# Aegaeon_REV_B_20130222.net
KiCad netlist of a schematic drawn in EAGLE
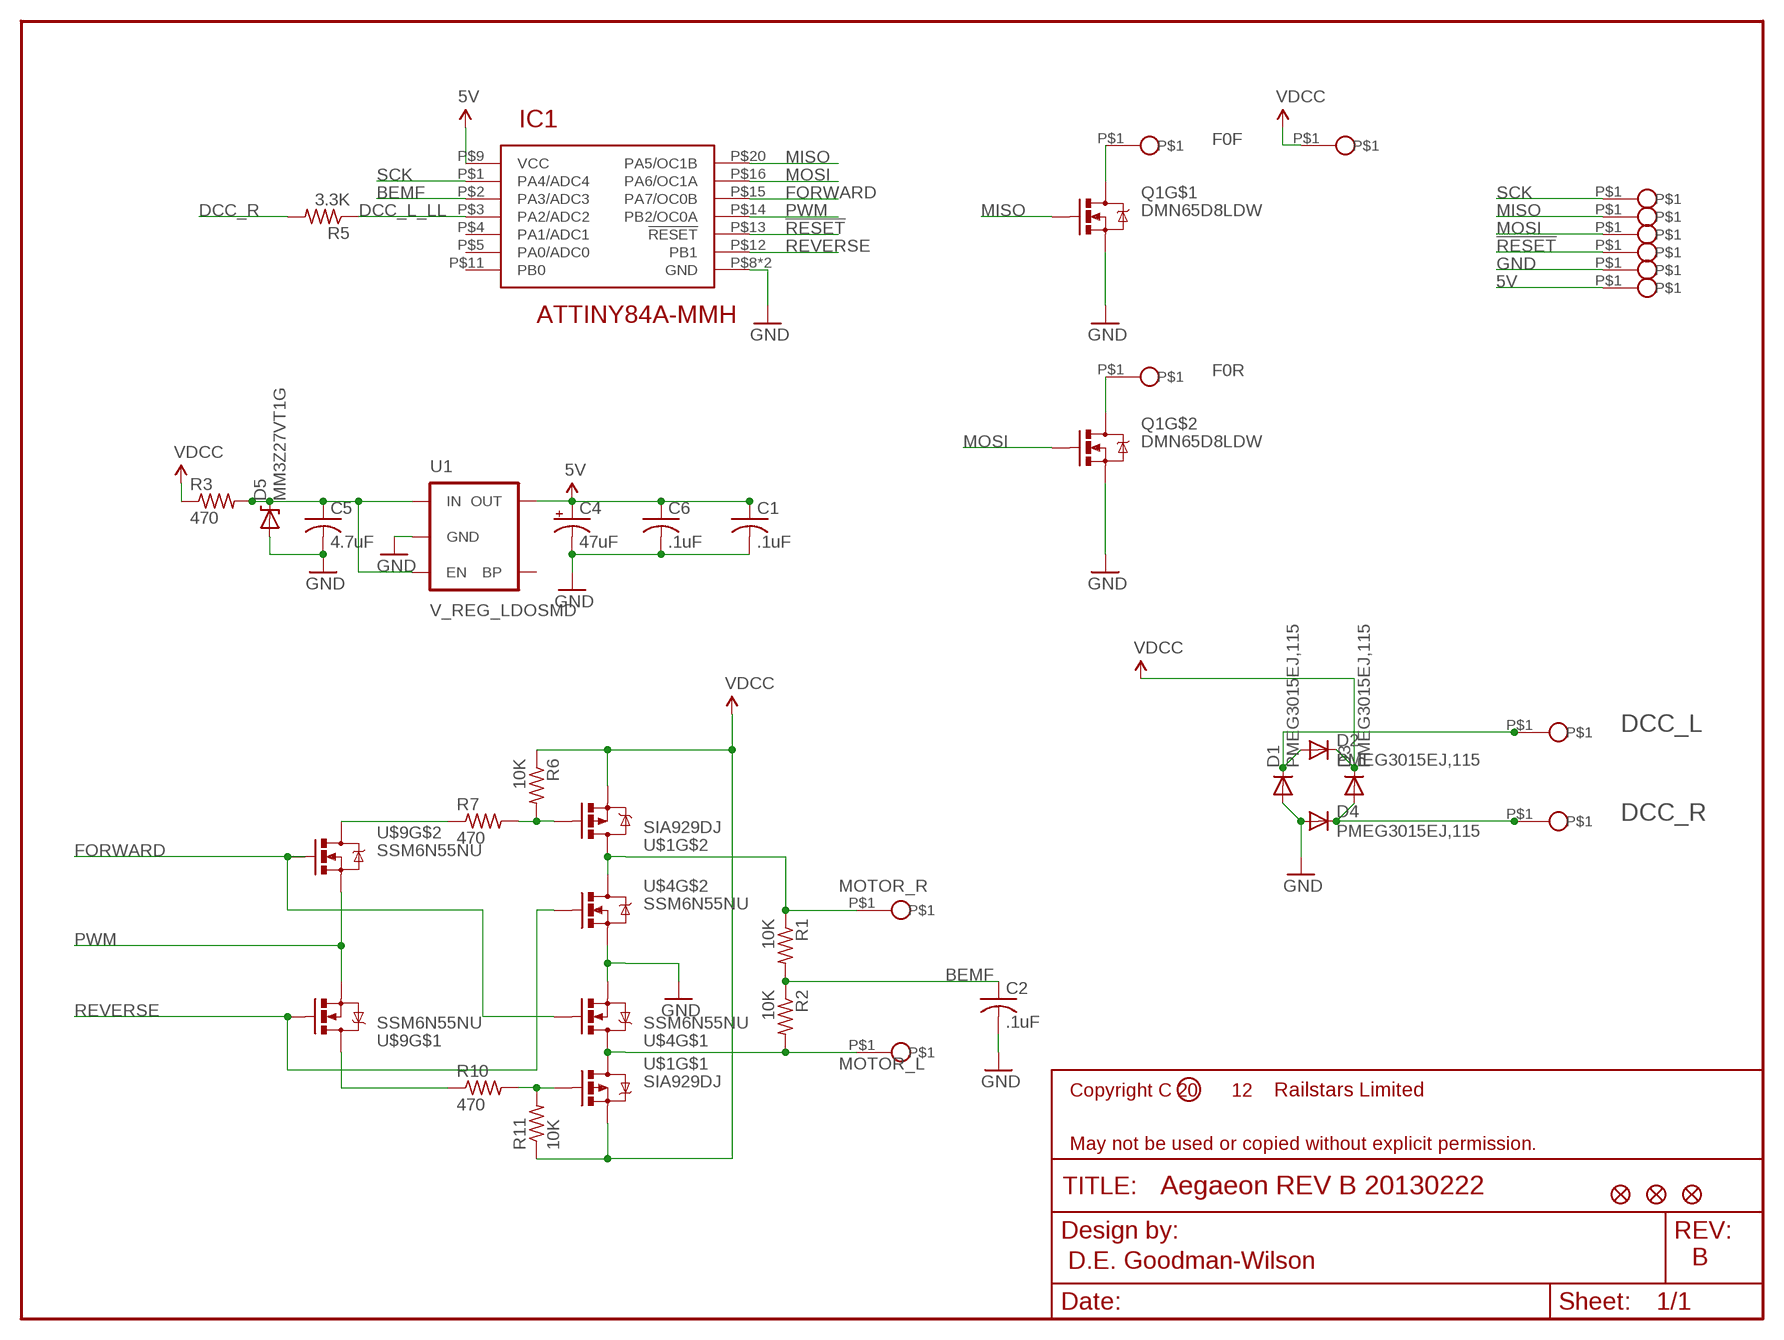
[diagram p0: schematic, sheet 1]

(export (version "E")
  (design (tool "Eeschema 10.0.6"))
  (components
    (comp (ref "C1")
      (value ".1uF")
      (footprint "eagle-import:C0201")
      (libsource (lib "eagle-import") (part "C-USC0201"))
    )
    (comp (ref "C2")
      (value ".1uF")
      (footprint "eagle-import:C0402")
      (libsource (lib "eagle-import") (part "C-USC0402"))
    )
    (comp (ref "C4")
      (value "47uF")
      (footprint "eagle-import:CPOL0603")
      (libsource (lib "eagle-import") (part "CPOL-USF980J476MMA"))
    )
    (comp (ref "C5")
      (value "4.7uF")
      (footprint "eagle-import:C0603")
      (libsource (lib "eagle-import") (part "C-USC0603"))
    )
    (comp (ref "C6")
      (value ".1uF")
      (footprint "eagle-import:C0402")
      (libsource (lib "eagle-import") (part "C-USC0402"))
    )
    (comp (ref "D1")
      (value "PMEG3015EJ,115")
      (footprint "eagle-import:SOD-323")
      (libsource (lib "eagle-import") (part "DIODESOD"))
    )
    (comp (ref "D2")
      (value "PMEG3015EJ,115")
      (footprint "eagle-import:SOD-323")
      (libsource (lib "eagle-import") (part "DIODESOD"))
    )
    (comp (ref "D3")
      (value "PMEG3015EJ,115")
      (footprint "eagle-import:SOD-323")
      (libsource (lib "eagle-import") (part "DIODESOD"))
    )
    (comp (ref "D4")
      (value "PMEG3015EJ,115")
      (footprint "eagle-import:SOD-323")
      (libsource (lib "eagle-import") (part "DIODESOD"))
    )
    (comp (ref "D5")
      (value "MM3Z27VT1G")
      (footprint "eagle-import:SOD-323")
      (libsource (lib "eagle-import") (part "DIODE-ZENER-BZT52"))
    )
    (comp (ref "DCC_L")
      (value "PAD1MM")
      (footprint "eagle-import:LED_SOLDER_PAD")
      (libsource (lib "eagle-import") (part "PAD1MM"))
    )
    (comp (ref "DCC_R")
      (value "PAD1MM")
      (footprint "eagle-import:LED_SOLDER_PAD")
      (libsource (lib "eagle-import") (part "PAD1MM"))
    )
    (comp (ref "IC1")
      (value "ATTINY84A-MMH")
      (footprint "eagle-import:VQFN-20")
      (libsource (lib "eagle-import") (part "ATTINY84A-MMH"))
    )
    (comp (ref "JP1")
      (value "FIDUCIALUFIDUCIAL")
      (footprint "eagle-import:MICRO-FIDUCIAL")
      (libsource (lib "eagle-import") (part "FIDUCIALUFIDUCIAL"))
    )
    (comp (ref "JP2")
      (value "FIDUCIALUFIDUCIAL")
      (footprint "eagle-import:MICRO-FIDUCIAL")
      (libsource (lib "eagle-import") (part "FIDUCIALUFIDUCIAL"))
    )
    (comp (ref "JP4")
      (value "FIDUCIALUFIDUCIAL")
      (footprint "eagle-import:MICRO-FIDUCIAL")
      (libsource (lib "eagle-import") (part "FIDUCIALUFIDUCIAL"))
    )
    (comp (ref "Q1")
      (value "DMN65D8LDW")
      (footprint "eagle-import:SOT363")
      (libsource (lib "eagle-import") (part "DMN65D8LDW"))
    )
    (comp (ref "R1")
      (value "10K")
      (footprint "eagle-import:R0201")
      (libsource (lib "eagle-import") (part "R-US_R0201"))
    )
    (comp (ref "R2")
      (value "10K")
      (footprint "eagle-import:R0201")
      (libsource (lib "eagle-import") (part "R-US_R0201"))
    )
    (comp (ref "R3")
      (value "470")
      (footprint "eagle-import:R0201")
      (libsource (lib "eagle-import") (part "R-US_R0201"))
    )
    (comp (ref "R5")
      (value "3.3K")
      (footprint "eagle-import:R0201")
      (libsource (lib "eagle-import") (part "R-US_R0201"))
    )
    (comp (ref "R6")
      (value "10K")
      (footprint "eagle-import:R0201")
      (libsource (lib "eagle-import") (part "R-US_R0201"))
    )
    (comp (ref "R7")
      (value "470")
      (footprint "eagle-import:R0201")
      (libsource (lib "eagle-import") (part "R-US_R0201"))
    )
    (comp (ref "R10")
      (value "470")
      (footprint "eagle-import:R0201")
      (libsource (lib "eagle-import") (part "R-US_R0201"))
    )
    (comp (ref "R11")
      (value "10K")
      (footprint "eagle-import:R0201")
      (libsource (lib "eagle-import") (part "R-US_R0201"))
    )
    (comp (ref "U$1")
      (value "SIA929DJ")
      (footprint "eagle-import:SC70-6L")
      (libsource (lib "eagle-import") (part "SIA929DJ"))
    )
    (comp (ref "U$2")
      (value "PAD1MM")
      (footprint "eagle-import:LED_SOLDER_PAD")
      (libsource (lib "eagle-import") (part "PAD1MM"))
    )
    (comp (ref "U$3")
      (value "PAD1MM")
      (footprint "eagle-import:LED_SOLDER_PAD")
      (libsource (lib "eagle-import") (part "PAD1MM"))
    )
    (comp (ref "U$4")
      (value "SSM6N55NU")
      (footprint "eagle-import:UDFN6")
      (libsource (lib "eagle-import") (part "SSM6N55NU"))
    )
    (comp (ref "U$5")
      (value "PAD1MM")
      (footprint "eagle-import:LED_SOLDER_PAD")
      (libsource (lib "eagle-import") (part "PAD1MM"))
    )
    (comp (ref "U$9")
      (value "SSM6N55NU")
      (footprint "eagle-import:UDFN6")
      (libsource (lib "eagle-import") (part "SSM6N55NU"))
    )
    (comp (ref "U$10")
      (value "PAD1MM")
      (footprint "eagle-import:LED_SOLDER_PAD")
      (libsource (lib "eagle-import") (part "PAD1MM"))
    )
    (comp (ref "U$11")
      (value "PAD1MM")
      (footprint "eagle-import:LED_SOLDER_PAD")
      (libsource (lib "eagle-import") (part "PAD1MM"))
    )
    (comp (ref "U$14")
      (value "PAD.75MM")
      (footprint "eagle-import:POGO_PAD")
      (libsource (lib "eagle-import") (part "PAD.75MM"))
    )
    (comp (ref "U$15")
      (value "PAD.75MM")
      (footprint "eagle-import:POGO_PAD")
      (libsource (lib "eagle-import") (part "PAD.75MM"))
    )
    (comp (ref "U$16")
      (value "PAD.75MM")
      (footprint "eagle-import:POGO_PAD")
      (libsource (lib "eagle-import") (part "PAD.75MM"))
    )
    (comp (ref "U$17")
      (value "PAD.75MM")
      (footprint "eagle-import:POGO_PAD")
      (libsource (lib "eagle-import") (part "PAD.75MM"))
    )
    (comp (ref "U$18")
      (value "PAD.75MM")
      (footprint "eagle-import:POGO_PAD")
      (libsource (lib "eagle-import") (part "PAD.75MM"))
    )
    (comp (ref "U$19")
      (value "PAD.75MM")
      (footprint "eagle-import:POGO_PAD")
      (libsource (lib "eagle-import") (part "PAD.75MM"))
    )
    (comp (ref "U1")
      (value "V_REG_LDOSMD")
      (footprint "eagle-import:SOT23-5")
      (libsource (lib "eagle-import") (part "V_REG_LDOSMD"))
    )
  )
  (nets
    (net (code "1") (name "/BEMF") (class "Default")
      (node (ref "C2") (pin "1") (pinfunction "1_1") (pintype "passive"))
      (node (ref "IC1") (pin "P$2") (pinfunction "PA3/ADC3_P$2") (pintype "bidirectional"))
      (node (ref "R1") (pin "2") (pinfunction "2_2") (pintype "passive"))
      (node (ref "R2") (pin "1") (pinfunction "1_1") (pintype "passive"))
    )
    (net (code "2") (name "/DCC_L") (class "Default")
      (node (ref "D1") (pin "1") (pinfunction "C_1") (pintype "passive"))
      (node (ref "D2") (pin "2") (pinfunction "A_2") (pintype "passive"))
      (node (ref "DCC_L") (pin "P$1") (pinfunction "P$1_P$1") (pintype "bidirectional"))
    )
    (net (code "3") (name "/DCC_L_LL") (class "Default")
      (node (ref "IC1") (pin "P$3") (pinfunction "PA2/ADC2_P$3") (pintype "bidirectional"))
      (node (ref "R5") (pin "1") (pinfunction "1_1") (pintype "passive"))
    )
    (net (code "4") (name "/DCC_R") (class "Default")
      (node (ref "D3") (pin "2") (pinfunction "A_2") (pintype "passive"))
      (node (ref "D4") (pin "1") (pinfunction "C_1") (pintype "passive"))
      (node (ref "DCC_R") (pin "P$1") (pinfunction "P$1_P$1") (pintype "bidirectional"))
      (node (ref "R5") (pin "2") (pinfunction "2_2") (pintype "passive"))
    )
    (net (code "5") (name "/F0F") (class "Default")
      (node (ref "Q1") (pin "P$4") (pinfunction "D_P$4") (pintype "passive"))
      (node (ref "U$10") (pin "P$1") (pinfunction "P$1_P$1") (pintype "bidirectional"))
    )
    (net (code "6") (name "/F0R") (class "Default")
      (node (ref "Q1") (pin "P$1") (pinfunction "D_P$1") (pintype "passive"))
      (node (ref "U$5") (pin "P$1") (pinfunction "P$1_P$1") (pintype "bidirectional"))
    )
    (net (code "7") (name "/FORWARD") (class "Default")
      (node (ref "IC1") (pin "P$15") (pinfunction "PA7/OC0B_P$15") (pintype "bidirectional"))
      (node (ref "U$4") (pin "G1") (pinfunction "G_G1") (pintype "passive"))
      (node (ref "U$9") (pin "G2") (pinfunction "G_G2") (pintype "passive"))
    )
    (net (code "8") (name "/MISO") (class "Default")
      (node (ref "IC1") (pin "P$20") (pinfunction "PA5/OC1B_P$20") (pintype "bidirectional"))
      (node (ref "Q1") (pin "P$2") (pinfunction "G_P$2") (pintype "passive"))
      (node (ref "U$15") (pin "P$1") (pinfunction "P$1_P$1") (pintype "bidirectional"))
    )
    (net (code "9") (name "/MOSI") (class "Default")
      (node (ref "IC1") (pin "P$16") (pinfunction "PA6/OC1A_P$16") (pintype "bidirectional"))
      (node (ref "Q1") (pin "P$5") (pinfunction "G_P$5") (pintype "passive"))
      (node (ref "U$16") (pin "P$1") (pinfunction "P$1_P$1") (pintype "bidirectional"))
    )
    (net (code "10") (name "/MOTOR_L") (class "Default")
      (node (ref "R2") (pin "2") (pinfunction "2_2") (pintype "passive"))
      (node (ref "U$1") (pin "D1") (pinfunction "D_D1") (pintype "passive"))
      (node (ref "U$1") (pin "D1$2") (pinfunction "D_D1$2") (pintype "passive"))
      (node (ref "U$3") (pin "P$1") (pinfunction "P$1_P$1") (pintype "bidirectional"))
      (node (ref "U$4") (pin "D1") (pinfunction "D_D1") (pintype "passive"))
      (node (ref "U$4") (pin "D1$1") (pinfunction "D_D1$1") (pintype "passive"))
    )
    (net (code "11") (name "/MOTOR_R") (class "Default")
      (node (ref "R1") (pin "1") (pinfunction "1_1") (pintype "passive"))
      (node (ref "U$1") (pin "D2") (pinfunction "D_D2") (pintype "passive"))
      (node (ref "U$1") (pin "D2$2") (pinfunction "D_D2$2") (pintype "passive"))
      (node (ref "U$2") (pin "P$1") (pinfunction "P$1_P$1") (pintype "bidirectional"))
      (node (ref "U$4") (pin "D2") (pinfunction "D_D2") (pintype "passive"))
      (node (ref "U$4") (pin "D2$2") (pinfunction "D_D2$2") (pintype "passive"))
    )
    (net (code "12") (name "/PWM") (class "Default")
      (node (ref "IC1") (pin "P$14") (pinfunction "PB2/OC0A_P$14") (pintype "bidirectional"))
      (node (ref "U$9") (pin "S1") (pinfunction "S_S1") (pintype "passive"))
      (node (ref "U$9") (pin "S2") (pinfunction "S_S2") (pintype "passive"))
    )
    (net (code "13") (name "/REVERSE") (class "Default")
      (node (ref "IC1") (pin "P$12") (pinfunction "PB1_P$12") (pintype "bidirectional"))
      (node (ref "U$4") (pin "G2") (pinfunction "G_G2") (pintype "passive"))
      (node (ref "U$9") (pin "G1") (pinfunction "G_G1") (pintype "passive"))
    )
    (net (code "14") (name "/SCK") (class "Default")
      (node (ref "IC1") (pin "P$1") (pinfunction "PA4/ADC4_P$1") (pintype "bidirectional"))
      (node (ref "U$14") (pin "P$1") (pinfunction "P$1_P$1") (pintype "bidirectional"))
    )
    (net (code "15") (name "/~{RESET}") (class "Default")
      (node (ref "IC1") (pin "P$13") (pinfunction "~{RESET}_P$13") (pintype "bidirectional"))
      (node (ref "U$17") (pin "P$1") (pinfunction "P$1_P$1") (pintype "bidirectional"))
    )
    (net (code "16") (name "5V") (class "Default")
      (node (ref "C1") (pin "1") (pinfunction "1_1") (pintype "passive"))
      (node (ref "C4") (pin "1") (pinfunction "+_1") (pintype "passive"))
      (node (ref "C6") (pin "1") (pinfunction "1_1") (pintype "passive"))
      (node (ref "IC1") (pin "P$9") (pinfunction "VCC_P$9") (pintype "bidirectional"))
      (node (ref "U$19") (pin "P$1") (pinfunction "P$1_P$1") (pintype "bidirectional"))
      (node (ref "U1") (pin "5") (pinfunction "OUT_5") (pintype "passive"))
    )
    (net (code "17") (name "GND") (class "Default")
      (node (ref "C1") (pin "2") (pinfunction "2_2") (pintype "passive"))
      (node (ref "C2") (pin "2") (pinfunction "2_2") (pintype "passive"))
      (node (ref "C4") (pin "2") (pinfunction "-_2") (pintype "passive"))
      (node (ref "C5") (pin "2") (pinfunction "2_2") (pintype "passive"))
      (node (ref "C6") (pin "2") (pinfunction "2_2") (pintype "passive"))
      (node (ref "D1") (pin "2") (pinfunction "A_2") (pintype "passive"))
      (node (ref "D4") (pin "2") (pinfunction "A_2") (pintype "passive"))
      (node (ref "D5") (pin "2") (pinfunction "A_2") (pintype "passive"))
      (node (ref "IC1") (pin "P$21") (pinfunction "GND_P$21") (pintype "bidirectional"))
      (node (ref "IC1") (pin "P$8") (pinfunction "GND_P$8") (pintype "bidirectional"))
      (node (ref "Q1") (pin "P$3") (pinfunction "S_P$3") (pintype "passive"))
      (node (ref "Q1") (pin "P$6") (pinfunction "S_P$6") (pintype "passive"))
      (node (ref "U$18") (pin "P$1") (pinfunction "P$1_P$1") (pintype "bidirectional"))
      (node (ref "U$4") (pin "S1") (pinfunction "S_S1") (pintype "passive"))
      (node (ref "U$4") (pin "S2") (pinfunction "S_S2") (pintype "passive"))
      (node (ref "U1") (pin "2") (pinfunction "GND_2") (pintype "input"))
    )
    (net (code "18") (name "Net-(D5-C)") (class "Default")
      (node (ref "C5") (pin "1") (pinfunction "1_1") (pintype "passive"))
      (node (ref "D5") (pin "1") (pinfunction "C_1") (pintype "passive"))
      (node (ref "R3") (pin "2") (pinfunction "2_2") (pintype "passive"))
      (node (ref "U1") (pin "1") (pinfunction "IN_1") (pintype "input"))
      (node (ref "U1") (pin "3") (pinfunction "EN_3") (pintype "input"))
    )
    (net (code "19") (name "Net-(R7-Pad1)") (class "Default")
      (node (ref "R7") (pin "1") (pinfunction "1_1") (pintype "passive"))
      (node (ref "U$9") (pin "D2") (pinfunction "D_D2") (pintype "passive"))
      (node (ref "U$9") (pin "D2$2") (pinfunction "D_D2$2") (pintype "passive"))
    )
    (net (code "20") (name "Net-(R10-Pad1)") (class "Default")
      (node (ref "R10") (pin "1") (pinfunction "1_1") (pintype "passive"))
      (node (ref "U$9") (pin "D1") (pinfunction "D_D1") (pintype "passive"))
      (node (ref "U$9") (pin "D1$1") (pinfunction "D_D1$1") (pintype "passive"))
    )
    (net (code "21") (name "Net-(U$1A-G)") (class "Default")
      (node (ref "R10") (pin "2") (pinfunction "2_2") (pintype "passive"))
      (node (ref "R11") (pin "2") (pinfunction "2_2") (pintype "passive"))
      (node (ref "U$1") (pin "G1") (pinfunction "G_G1") (pintype "passive"))
    )
    (net (code "22") (name "Net-(U$1B-G)") (class "Default")
      (node (ref "R6") (pin "2") (pinfunction "2_2") (pintype "passive"))
      (node (ref "R7") (pin "2") (pinfunction "2_2") (pintype "passive"))
      (node (ref "U$1") (pin "G2") (pinfunction "G_G2") (pintype "passive"))
    )
    (net (code "23") (name "VDCC") (class "Default")
      (node (ref "D2") (pin "1") (pinfunction "C_1") (pintype "passive"))
      (node (ref "D3") (pin "1") (pinfunction "C_1") (pintype "passive"))
      (node (ref "R11") (pin "1") (pinfunction "1_1") (pintype "passive"))
      (node (ref "R3") (pin "1") (pinfunction "1_1") (pintype "passive"))
      (node (ref "R6") (pin "1") (pinfunction "1_1") (pintype "passive"))
      (node (ref "U$1") (pin "S1") (pinfunction "S_S1") (pintype "passive"))
      (node (ref "U$1") (pin "S2") (pinfunction "S_S2") (pintype "passive"))
      (node (ref "U$11") (pin "P$1") (pinfunction "P$1_P$1") (pintype "bidirectional"))
    )
    (net (code "24") (name "unconnected-(IC1-PA0{slash}ADC0-PadP$5)") (class "Default")
      (node (ref "IC1") (pin "P$5") (pinfunction "PA0/ADC0_P$5") (pintype "bidirectional"))
    )
    (net (code "25") (name "unconnected-(IC1-PA1{slash}ADC1-PadP$4)") (class "Default")
      (node (ref "IC1") (pin "P$4") (pinfunction "PA1/ADC1_P$4") (pintype "bidirectional"))
    )
    (net (code "26") (name "unconnected-(IC1-PB0-PadP$11)") (class "Default")
      (node (ref "IC1") (pin "P$11") (pinfunction "PB0_P$11") (pintype "bidirectional"))
    )
    (net (code "27") (name "unconnected-(U1-BP-Pad4)") (class "Default")
      (node (ref "U1") (pin "4") (pinfunction "BP_4") (pintype "input"))
    )
  )
)
